# SW_S_5.net
KiCad netlist of a schematic drawn in Altium Designer
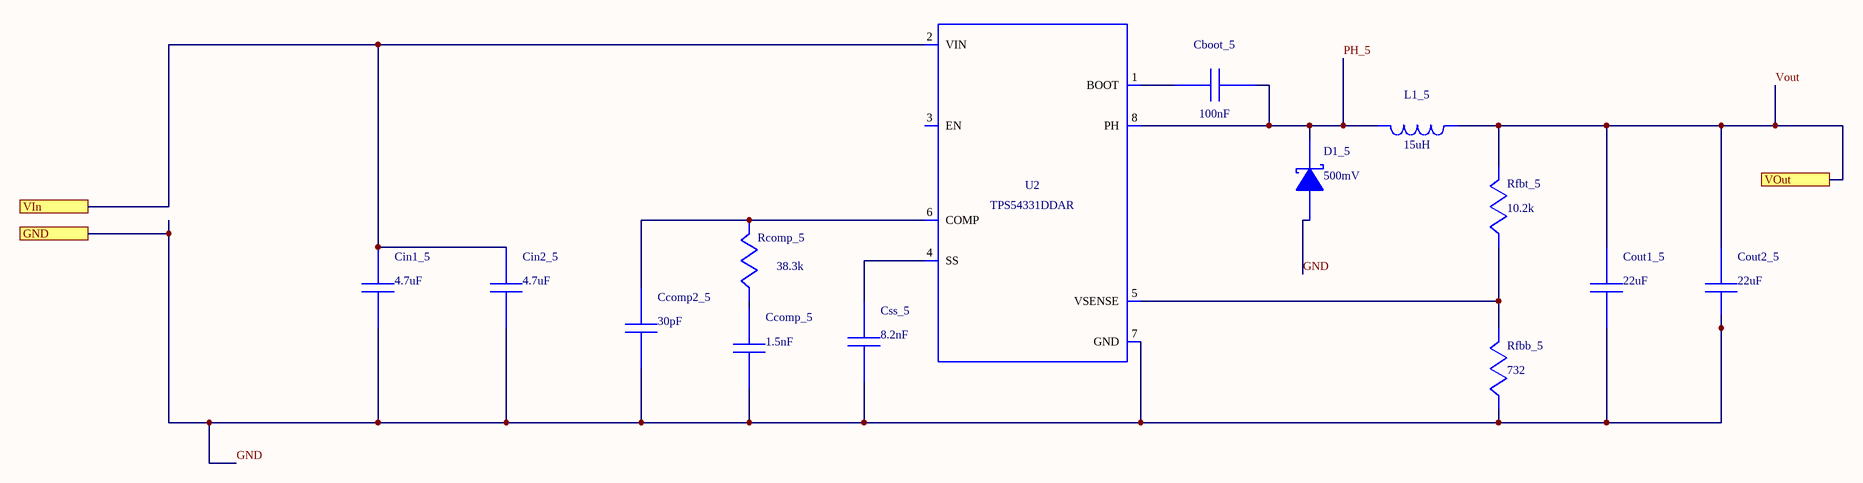
[diagram p0: SW_S_5.SchDoc]

(export (version "E")
  (design (tool "Eeschema 10.0.6"))
  (components
    (comp (ref "Cboot_5")
      (value "100nF")
      (footprint "1608[0603]")
      (description "C1608X7R1E104K")
      (libsource (lib "TI WEBENCH") (part "Cboot"))
    )
    (comp (ref "Ccomp2_5")
      (value "30pF")
      (footprint "6-0805_M")
      (description "CL21C300JBANNNC")
      (libsource (lib "TI WEBENCH") (part "Ccomp2"))
    )
    (comp (ref "Ccomp_5")
      (value "1.5nF")
      (footprint "6-0805_M")
      (description "CC0805KRX7R9BB15")
      (fields (field (name "MANUFACTURER PART NUMBER") "CC0805KRX7R9BB152"))
      (libsource (lib "TI WEBENCH") (part "Ccomp"))
    )
    (comp (ref "Cin1_5")
      (value "4.7uF")
      (footprint "C1210_M")
      (description "GRM32ER71H475KA8")
      (fields (field (name "MANUFACTURER PART NUMBER") "GRM32ER71H475KA88L"))
      (libsource (lib "TI WEBENCH") (part "Cin"))
    )
    (comp (ref "Cin2_5")
      (value "4.7uF")
      (footprint "C1210_M")
      (description "GRM32ER71H475KA8")
      (fields (field (name "MANUFACTURER PART NUMBER") "GRM32ER71H475KA88L"))
      (libsource (lib "TI WEBENCH") (part "Cin"))
    )
    (comp (ref "Cout1_5")
      (value "22uF")
      (footprint "C1210_M")
      (description "GRM32ER61E226KE1")
      (fields (field (name "MANUFACTURER PART NUMBER") "GRM32ER61E226KE15L"))
      (libsource (lib "TI WEBENCH") (part "Cout"))
    )
    (comp (ref "Cout2_5")
      (value "22uF")
      (footprint "C1210_M")
      (description "GRM32ER61E226KE1")
      (fields (field (name "MANUFACTURER PART NUMBER") "GRM32ER61E226KE15L"))
      (libsource (lib "TI WEBENCH") (part "Cout"))
    )
    (comp (ref "Css_5")
      (value "8.2nF")
      (footprint "1608[0603]")
      (description "GRM188R71E822KA0")
      (fields (field (name "MANUFACTURER PART NUMBER") "GRM188R71E822KA01D"))
      (libsource (lib "TI WEBENCH") (part "Css"))
    )
    (comp (ref "D1_5")
      (value "500mV")
      (footprint "SMA Diode Package")
      (description "B340A-13-F")
      (libsource (lib "TI WEBENCH") (part "D1"))
    )
    (comp (ref "L1_5")
      (value "15uH")
      (footprint "SRR1260")
      (description "SRR1260-150M")
      (libsource (lib "TI WEBENCH") (part "L1"))
    )
    (comp (ref "Rcomp_5")
      (value "38.3k")
      (footprint "6-0805_M")
      (description "CRCW080538K3FKEA")
      (libsource (lib "TI WEBENCH") (part "Rcomp"))
    )
    (comp (ref "Rfbb_5")
      (value "732")
      (footprint "6-0805_M")
      (description "CRCW0805732RFKEA")
      (libsource (lib "TI WEBENCH") (part "Rfbb"))
    )
    (comp (ref "Rfbt_5")
      (value "10.2k")
      (footprint "6-0805_M")
      (description "CRCW080510K2FKEA")
      (libsource (lib "TI WEBENCH") (part "Rfbt"))
    )
    (comp (ref "U2")
      (value "TPS54331DDAR")
      (footprint "TI-D8_N")
      (fields (field (name "PACKAGEREFERENCE") "TPS54331DDAR"))
      (libsource (lib "TI WEBENCH") (part "U1"))
    )
  )
  (nets
    (net (code "1") (name "/GND") (class "Default")
      (node (ref "Ccomp2_5") (pin "2") (pinfunction "2_2") (pintype "passive"))
      (node (ref "Ccomp_5") (pin "2") (pinfunction "2_2") (pintype "passive"))
      (node (ref "Cin1_5") (pin "2") (pinfunction "2_2") (pintype "passive"))
      (node (ref "Cin2_5") (pin "2") (pinfunction "2_2") (pintype "passive"))
      (node (ref "Cout1_5") (pin "2") (pinfunction "2_2") (pintype "passive"))
      (node (ref "Cout2_5") (pin "2") (pinfunction "2_2") (pintype "passive"))
      (node (ref "Css_5") (pin "2") (pinfunction "2_2") (pintype "passive"))
      (node (ref "D1_5") (pin "2") (pinfunction "A_2") (pintype "passive"))
      (node (ref "Rfbb_5") (pin "2") (pinfunction "2_2") (pintype "passive"))
      (node (ref "U2") (pin "7") (pinfunction "GND_7") (pintype "passive"))
    )
    (net (code "2") (name "/PH_5") (class "Default")
      (node (ref "Cboot_5") (pin "2") (pinfunction "2_2") (pintype "passive"))
      (node (ref "D1_5") (pin "1") (pinfunction "K_1") (pintype "passive"))
      (node (ref "L1_5") (pin "1") (pinfunction "1_1") (pintype "passive"))
      (node (ref "U2") (pin "8") (pinfunction "PH_8") (pintype "passive"))
    )
    (net (code "3") (name "/VIn") (class "Default")
      (node (ref "Cin1_5") (pin "1") (pinfunction "1_1") (pintype "passive"))
      (node (ref "Cin2_5") (pin "1") (pinfunction "1_1") (pintype "passive"))
      (node (ref "U2") (pin "2") (pinfunction "VIN_2") (pintype "passive"))
    )
    (net (code "4") (name "/Vout") (class "Default")
      (node (ref "Cout1_5") (pin "1") (pinfunction "1_1") (pintype "passive"))
      (node (ref "Cout2_5") (pin "1") (pinfunction "1_1") (pintype "passive"))
      (node (ref "L1_5") (pin "2") (pinfunction "2_2") (pintype "passive"))
      (node (ref "Rfbt_5") (pin "1") (pinfunction "1_1") (pintype "passive"))
    )
    (net (code "5") (name "Net-(Ccomp_5-Pad1)") (class "Default")
      (node (ref "Ccomp_5") (pin "1") (pinfunction "1_1") (pintype "passive"))
      (node (ref "Rcomp_5") (pin "2") (pinfunction "2_2") (pintype "passive"))
    )
    (net (code "6") (name "Net-(U2-BOOT)") (class "Default")
      (node (ref "Cboot_5") (pin "1") (pinfunction "1_1") (pintype "passive"))
      (node (ref "U2") (pin "1") (pinfunction "BOOT_1") (pintype "passive"))
    )
    (net (code "7") (name "Net-(U2-COMP)") (class "Default")
      (node (ref "Ccomp2_5") (pin "1") (pinfunction "1_1") (pintype "passive"))
      (node (ref "Rcomp_5") (pin "1") (pinfunction "1_1") (pintype "passive"))
      (node (ref "U2") (pin "6") (pinfunction "COMP_6") (pintype "passive"))
    )
    (net (code "8") (name "Net-(U2-SS)") (class "Default")
      (node (ref "Css_5") (pin "1") (pinfunction "1_1") (pintype "passive"))
      (node (ref "U2") (pin "4") (pinfunction "SS_4") (pintype "passive"))
    )
    (net (code "9") (name "Net-(U2-VSENSE)") (class "Default")
      (node (ref "Rfbb_5") (pin "1") (pinfunction "1_1") (pintype "passive"))
      (node (ref "Rfbt_5") (pin "2") (pinfunction "2_2") (pintype "passive"))
      (node (ref "U2") (pin "5") (pinfunction "VSENSE_5") (pintype "passive"))
    )
    (net (code "10") (name "unconnected-(U2-EN-Pad3)") (class "Default")
      (node (ref "U2") (pin "3") (pinfunction "EN_3") (pintype "passive"))
    )
  )
)
